# Auxiliary.net
KiCad netlist of a schematic drawn in Altium Designer
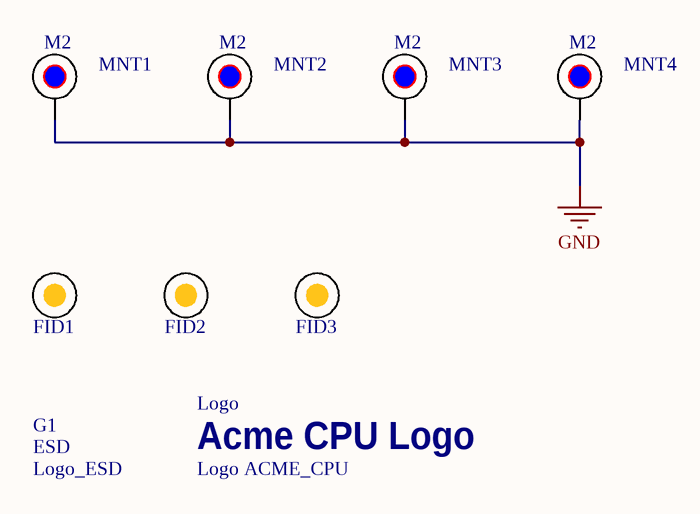
[diagram p0: Auxiliary.SchDoc]

(export (version "E")
  (design (tool "Eeschema 10.0.6"))
  (components
    (comp (ref "FID1")
      (value "N/A")
      (footprint "Fiducial")
      (description "Fiducial mark.  There is nothing to buy or mount.")
      (libsource (lib "BLDC_Motor_Driver") (part "Fiducial"))
    )
    (comp (ref "FID2")
      (value "N/A")
      (footprint "Fiducial")
      (description "Fiducial mark.  There is nothing to buy or mount.")
      (libsource (lib "BLDC_Motor_Driver") (part "Fiducial"))
    )
    (comp (ref "FID3")
      (value "N/A")
      (footprint "Fiducial")
      (description "Fiducial mark.  There is nothing to buy or mount.")
      (libsource (lib "BLDC_Motor_Driver") (part "Fiducial"))
    )
    (comp (ref "G1")
      (value "Logo_ESD")
      (footprint "Logo_ESD")
      (libsource (lib "altium-import") (part "root_0_Logo_ESD_"))
    )
    (comp (ref "Logo")
      (value "Logo ACME_CPU")
      (footprint "LOGO_ACME_CPU")
      (libsource (lib "BLDC_Motor_Driver") (part "Logo ACME_CPU"))
    )
    (comp (ref "MNT1")
      (value "MountHole M2. Nothing to buy or mount")
      (footprint "MountHole_M2")
      (description "PCB Mount Hole. There is nothing to buy or mount.")
      (libsource (lib "BLDC_Motor_Driver") (part "MountHole_M2"))
    )
    (comp (ref "MNT2")
      (value "MountHole M2. Nothing to buy or mount")
      (footprint "MountHole_M2")
      (description "PCB Mount Hole. There is nothing to buy or mount.")
      (libsource (lib "BLDC_Motor_Driver") (part "MountHole_M2"))
    )
    (comp (ref "MNT3")
      (value "MountHole M2. Nothing to buy or mount")
      (footprint "MountHole_M2")
      (description "PCB Mount Hole. There is nothing to buy or mount.")
      (libsource (lib "BLDC_Motor_Driver") (part "MountHole_M2"))
    )
    (comp (ref "MNT4")
      (value "MountHole M2. Nothing to buy or mount")
      (footprint "MountHole_M2")
      (description "PCB Mount Hole. There is nothing to buy or mount.")
      (libsource (lib "BLDC_Motor_Driver") (part "MountHole_M2"))
    )
  )
  (nets
    (net (code "1") (name "GND") (class "Default")
      (node (ref "MNT1") (pin "1") (pintype "passive"))
      (node (ref "MNT2") (pin "1") (pintype "passive"))
      (node (ref "MNT3") (pin "1") (pintype "passive"))
      (node (ref "MNT4") (pin "1") (pintype "passive"))
    )
  )
)
